# control_bat.net
KiCad netlist of a schematic drawn in EAGLE
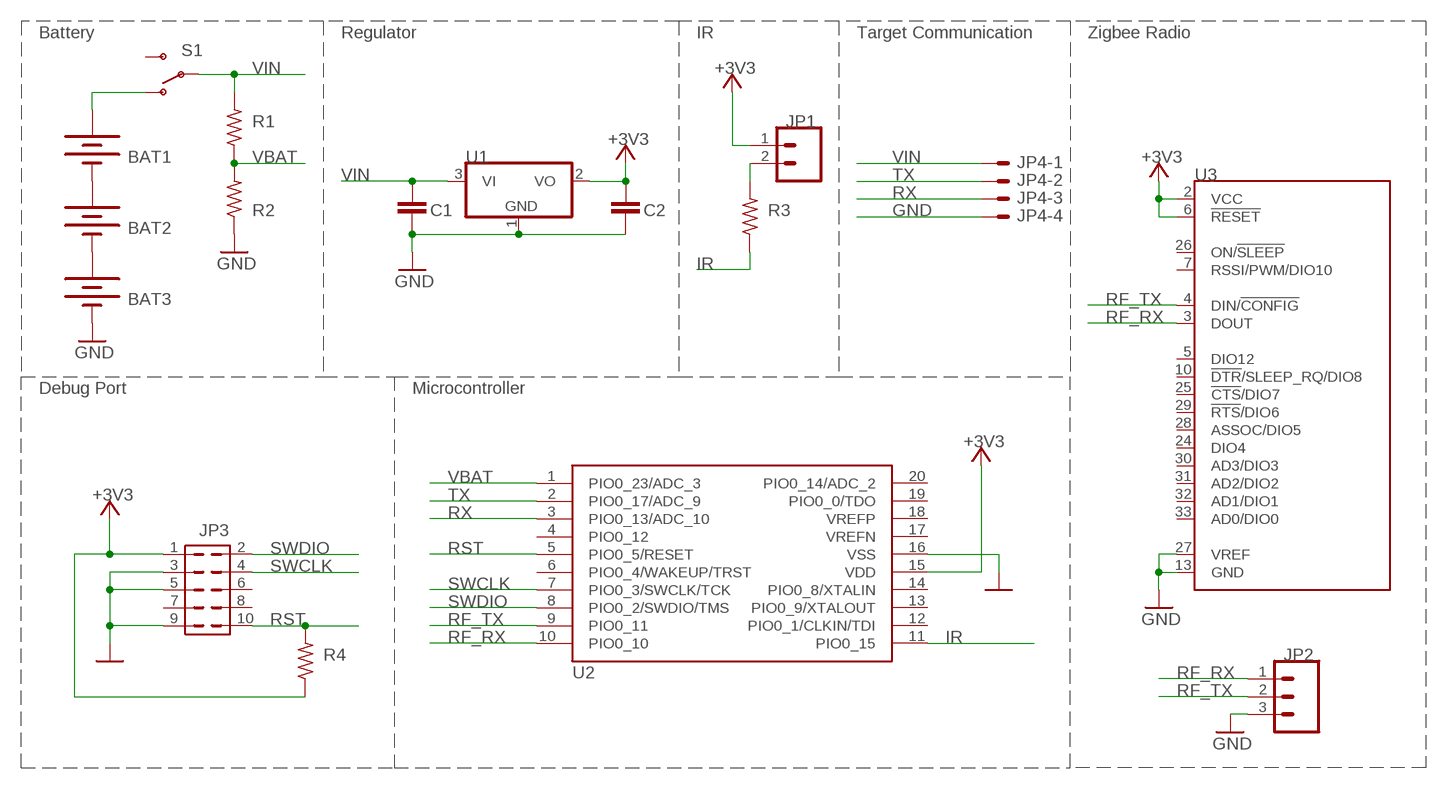
[diagram p0: schematic, sheet 1]

(export (version "E")
  (design (tool "Eeschema 10.0.6"))
  (components
    (comp (ref "BAT1")
      (value "BATTERYAAA-KIT")
      (footprint "eagle-import:BATTERY-AAA-KIT")
      (libsource (lib "eagle-import") (part "BATTERYAAA-KIT"))
    )
    (comp (ref "BAT2")
      (value "BATTERYAAA-KIT")
      (footprint "eagle-import:BATTERY-AAA-KIT")
      (libsource (lib "eagle-import") (part "BATTERYAAA-KIT"))
    )
    (comp (ref "BAT3")
      (value "BATTERYAAA-KIT")
      (footprint "eagle-import:BATTERY-AAA-KIT")
      (libsource (lib "eagle-import") (part "BATTERYAAA-KIT"))
    )
    (comp (ref "C1")
      (value "C1608X5R1C106M080AB")
      (footprint "eagle-import:0603-CAP")
      (libsource (lib "eagle-import") (part "CAP0603-CAP"))
    )
    (comp (ref "C2")
      (value "C1608X5R1C106M080AB")
      (footprint "eagle-import:0603-CAP")
      (libsource (lib "eagle-import") (part "CAP0603-CAP"))
    )
    (comp (ref "JP1")
      (value "M02PTH")
      (footprint "eagle-import:1X02")
      (libsource (lib "eagle-import") (part "M02PTH"))
    )
    (comp (ref "JP2")
      (value "M03PTH")
      (footprint "eagle-import:1X03")
      (libsource (lib "eagle-import") (part "M03PTH"))
    )
    (comp (ref "JP3")
      (value "FTSH-105-01-L")
      (footprint "eagle-import:FTSH-105-01-XXX-DV-K")
      (libsource (lib "eagle-import") (part "FTSH-105"))
    )
    (comp (ref "JP4")
      (value "798-DF134P125V20")
      (footprint "eagle-import:53398-04")
      (libsource (lib "eagle-import") (part "53?-04398"))
    )
    (comp (ref "R1")
      (value "71-CRCW0603-10K-E3")
      (footprint "eagle-import:R0603")
      (libsource (lib "eagle-import") (part "R-US_R0603"))
    )
    (comp (ref "R2")
      (value "71-CRCW0603-10K-E3")
      (footprint "eagle-import:R0603")
      (libsource (lib "eagle-import") (part "R-US_R0603"))
    )
    (comp (ref "R3")
      (value "71-CRCW0603220RFKEB")
      (footprint "eagle-import:R0603")
      (libsource (lib "eagle-import") (part "R-US_R0603"))
    )
    (comp (ref "R4")
      (value "71-CRCW0603-10K-E3")
      (footprint "eagle-import:R0603")
      (libsource (lib "eagle-import") (part "R-US_R0603"))
    )
    (comp (ref "S1")
      (value "612-EG1270")
      (footprint "eagle-import:EG1270")
      (libsource (lib "eagle-import") (part "SWITCH-SPST"))
    )
    (comp (ref "U1")
      (value "579-MCP1703T-3002ECB")
      (footprint "eagle-import:SOT23")
      (libsource (lib "eagle-import") (part "MCP1703CB"))
    )
    (comp (ref "U2")
      (value "771-LPC824M201JDH20J")
      (footprint "eagle-import:TSSOP20")
      (libsource (lib "eagle-import") (part "LPC824"))
    )
    (comp (ref "U3")
      (value "888-XB24CZ7PIS-004")
      (footprint "eagle-import:XBEE-SMT")
      (libsource (lib "eagle-import") (part "XBEE-SMT"))
    )
  )
  (nets
    (net (code "1") (name "+3V3") (class "Default")
      (node (ref "C2") (pin "1") (pinfunction "1_1") (pintype "passive"))
      (node (ref "JP1") (pin "1") (pinfunction "1_1") (pintype "passive"))
      (node (ref "JP3") (pin "1") (pinfunction "1_1") (pintype "passive"))
      (node (ref "R4") (pin "1") (pinfunction "1_1") (pintype "passive"))
      (node (ref "U1") (pin "2") (pinfunction "VO_2") (pintype "passive"))
      (node (ref "U2") (pin "15") (pinfunction "VDD_15") (pintype "bidirectional"))
      (node (ref "U3") (pin "2") (pinfunction "VCC_2") (pintype "power_in"))
      (node (ref "U3") (pin "6") (pinfunction "~{RESET}_6") (pintype "input"))
    )
    (net (code "2") (name "/IR") (class "Default")
      (node (ref "R3") (pin "1") (pinfunction "1_1") (pintype "passive"))
      (node (ref "U2") (pin "11") (pinfunction "PIO0_15_11") (pintype "bidirectional"))
    )
    (net (code "3") (name "/RF_RX") (class "Default")
      (node (ref "JP2") (pin "1") (pinfunction "1_1") (pintype "passive"))
      (node (ref "U2") (pin "10") (pinfunction "PIO0_10_10") (pintype "bidirectional"))
      (node (ref "U3") (pin "3") (pinfunction "DOUT_3") (pintype "output"))
    )
    (net (code "4") (name "/RF_TX") (class "Default")
      (node (ref "JP2") (pin "2") (pinfunction "2_2") (pintype "passive"))
      (node (ref "U2") (pin "9") (pinfunction "PIO0_11_9") (pintype "bidirectional"))
      (node (ref "U3") (pin "4") (pinfunction "DIN/~{CONFIG}_4") (pintype "input"))
    )
    (net (code "5") (name "/RST") (class "Default")
      (node (ref "JP3") (pin "10") (pinfunction "10_10") (pintype "passive"))
      (node (ref "R4") (pin "2") (pinfunction "2_2") (pintype "passive"))
      (node (ref "U2") (pin "5") (pinfunction "PIO0_5/RESET_5") (pintype "bidirectional"))
    )
    (net (code "6") (name "/RX") (class "Default")
      (node (ref "JP4") (pin "3") (pinfunction "S_3") (pintype "passive"))
      (node (ref "U2") (pin "3") (pinfunction "PIO0_13/ADC_10_3") (pintype "bidirectional"))
    )
    (net (code "7") (name "/SWCLK") (class "Default")
      (node (ref "JP3") (pin "4") (pinfunction "4_4") (pintype "passive"))
      (node (ref "U2") (pin "7") (pinfunction "PIO0_3/SWCLK/TCK_7") (pintype "bidirectional"))
    )
    (net (code "8") (name "/SWDIO") (class "Default")
      (node (ref "JP3") (pin "2") (pinfunction "2_2") (pintype "passive"))
      (node (ref "U2") (pin "8") (pinfunction "PIO0_2/SWDIO/TMS_8") (pintype "bidirectional"))
    )
    (net (code "9") (name "/TX") (class "Default")
      (node (ref "JP4") (pin "2") (pinfunction "S_2") (pintype "passive"))
      (node (ref "U2") (pin "2") (pinfunction "PIO0_17/ADC_9_2") (pintype "bidirectional"))
    )
    (net (code "10") (name "/VBAT") (class "Default")
      (node (ref "R1") (pin "1") (pinfunction "1_1") (pintype "passive"))
      (node (ref "R2") (pin "2") (pinfunction "2_2") (pintype "passive"))
      (node (ref "U2") (pin "1") (pinfunction "PIO0_23/ADC_3_1") (pintype "bidirectional"))
    )
    (net (code "11") (name "/VIN") (class "Default")
      (node (ref "C1") (pin "1") (pinfunction "1_1") (pintype "passive"))
      (node (ref "JP4") (pin "1") (pinfunction "S_1") (pintype "passive"))
      (node (ref "R1") (pin "2") (pinfunction "2_2") (pintype "passive"))
      (node (ref "S1") (pin "P$2") (pinfunction "P_P$2") (pintype "passive"))
      (node (ref "U1") (pin "3") (pinfunction "VI_3") (pintype "input"))
    )
    (net (code "12") (name "GND") (class "Default")
      (node (ref "BAT3") (pin "GND@1") (pinfunction "-_GND@1") (pintype "power_in"))
      (node (ref "C1") (pin "2") (pinfunction "2_2") (pintype "passive"))
      (node (ref "C2") (pin "2") (pinfunction "2_2") (pintype "passive"))
      (node (ref "JP2") (pin "3") (pinfunction "3_3") (pintype "passive"))
      (node (ref "JP3") (pin "3") (pinfunction "3_3") (pintype "passive"))
      (node (ref "JP3") (pin "5") (pinfunction "5_5") (pintype "passive"))
      (node (ref "JP3") (pin "9") (pinfunction "9_9") (pintype "passive"))
      (node (ref "JP4") (pin "4") (pinfunction "S_4") (pintype "passive"))
      (node (ref "R2") (pin "1") (pinfunction "1_1") (pintype "passive"))
      (node (ref "U1") (pin "1") (pinfunction "GND_1") (pintype "passive"))
      (node (ref "U2") (pin "16") (pinfunction "VSS_16") (pintype "bidirectional"))
      (node (ref "U3") (pin "13") (pinfunction "GND_13") (pintype "power_in"))
      (node (ref "U3") (pin "27") (pinfunction "VREF_27") (pintype "input"))
    )
    (net (code "13") (name "Net-(BAT1-+)") (class "Default")
      (node (ref "BAT1") (pin "PWR@1") (pinfunction "+_PWR@1") (pintype "power_in"))
      (node (ref "S1") (pin "P$1") (pinfunction "O_P$1") (pintype "passive"))
    )
    (net (code "14") (name "Net-(BAT1--)") (class "Default")
      (node (ref "BAT1") (pin "GND@1") (pinfunction "-_GND@1") (pintype "power_in"))
      (node (ref "BAT2") (pin "PWR@1") (pinfunction "+_PWR@1") (pintype "power_in"))
    )
    (net (code "15") (name "Net-(BAT2--)") (class "Default")
      (node (ref "BAT2") (pin "GND@1") (pinfunction "-_GND@1") (pintype "power_in"))
      (node (ref "BAT3") (pin "PWR@1") (pinfunction "+_PWR@1") (pintype "power_in"))
    )
    (net (code "16") (name "Net-(JP1-Pad2)") (class "Default")
      (node (ref "JP1") (pin "2") (pinfunction "2_2") (pintype "passive"))
      (node (ref "R3") (pin "2") (pinfunction "2_2") (pintype "passive"))
    )
    (net (code "17") (name "unconnected-(JP3-Pad6)") (class "Default")
      (node (ref "JP3") (pin "6") (pinfunction "6_6") (pintype "passive"))
    )
    (net (code "18") (name "unconnected-(JP3-Pad7)") (class "Default")
      (node (ref "JP3") (pin "7") (pinfunction "7_7") (pintype "passive"))
    )
    (net (code "19") (name "unconnected-(JP3-Pad8)") (class "Default")
      (node (ref "JP3") (pin "8") (pinfunction "8_8") (pintype "passive"))
    )
    (net (code "20") (name "unconnected-(S1-S-PadP$3)") (class "Default")
      (node (ref "S1") (pin "P$3") (pinfunction "S_P$3") (pintype "passive"))
    )
    (net (code "21") (name "unconnected-(U2-PIO0_0{slash}TDO-Pad19)") (class "Default")
      (node (ref "U2") (pin "19") (pinfunction "PIO0_0/TDO_19") (pintype "bidirectional"))
    )
    (net (code "22") (name "unconnected-(U2-PIO0_1{slash}CLKIN{slash}TDI-Pad12)") (class "Default")
      (node (ref "U2") (pin "12") (pinfunction "PIO0_1/CLKIN/TDI_12") (pintype "bidirectional"))
    )
    (net (code "23") (name "unconnected-(U2-PIO0_4{slash}WAKEUP{slash}TRST-Pad6)") (class "Default")
      (node (ref "U2") (pin "6") (pinfunction "PIO0_4/WAKEUP/TRST_6") (pintype "bidirectional"))
    )
    (net (code "24") (name "unconnected-(U2-PIO0_8{slash}XTALIN-Pad14)") (class "Default")
      (node (ref "U2") (pin "14") (pinfunction "PIO0_8/XTALIN_14") (pintype "bidirectional"))
    )
    (net (code "25") (name "unconnected-(U2-PIO0_9{slash}XTALOUT-Pad13)") (class "Default")
      (node (ref "U2") (pin "13") (pinfunction "PIO0_9/XTALOUT_13") (pintype "bidirectional"))
    )
    (net (code "26") (name "unconnected-(U2-PIO0_12-Pad4)") (class "Default")
      (node (ref "U2") (pin "4") (pinfunction "PIO0_12_4") (pintype "bidirectional"))
    )
    (net (code "27") (name "unconnected-(U2-PIO0_14{slash}ADC_2-Pad20)") (class "Default")
      (node (ref "U2") (pin "20") (pinfunction "PIO0_14/ADC_2_20") (pintype "bidirectional"))
    )
    (net (code "28") (name "unconnected-(U2-VREFN-Pad17)") (class "Default")
      (node (ref "U2") (pin "17") (pinfunction "VREFN_17") (pintype "bidirectional"))
    )
    (net (code "29") (name "unconnected-(U2-VREFP-Pad18)") (class "Default")
      (node (ref "U2") (pin "18") (pinfunction "VREFP_18") (pintype "bidirectional"))
    )
    (net (code "30") (name "unconnected-(U3-AD0{slash}DIO0-Pad33)") (class "Default")
      (node (ref "U3") (pin "33") (pinfunction "AD0/DIO0_33") (pintype "bidirectional"))
    )
    (net (code "31") (name "unconnected-(U3-AD1{slash}DIO1-Pad32)") (class "Default")
      (node (ref "U3") (pin "32") (pinfunction "AD1/DIO1_32") (pintype "bidirectional"))
    )
    (net (code "32") (name "unconnected-(U3-AD2{slash}DIO2-Pad31)") (class "Default")
      (node (ref "U3") (pin "31") (pinfunction "AD2/DIO2_31") (pintype "bidirectional"))
    )
    (net (code "33") (name "unconnected-(U3-AD3{slash}DIO3-Pad30)") (class "Default")
      (node (ref "U3") (pin "30") (pinfunction "AD3/DIO3_30") (pintype "bidirectional"))
    )
    (net (code "34") (name "unconnected-(U3-ASSOC{slash}DIO5-Pad28)") (class "Default")
      (node (ref "U3") (pin "28") (pinfunction "ASSOC/DIO5_28") (pintype "bidirectional"))
    )
    (net (code "35") (name "unconnected-(U3-DIO4-Pad24)") (class "Default")
      (node (ref "U3") (pin "24") (pinfunction "DIO4_24") (pintype "bidirectional"))
    )
    (net (code "36") (name "unconnected-(U3-DIO12-Pad5)") (class "Default")
      (node (ref "U3") (pin "5") (pinfunction "DIO12_5") (pintype "bidirectional"))
    )
    (net (code "37") (name "unconnected-(U3-ON{slash}~{SLEEP}-Pad26)") (class "Default")
      (node (ref "U3") (pin "26") (pinfunction "ON/~{SLEEP}_26") (pintype "output"))
    )
    (net (code "38") (name "unconnected-(U3-RSSI{slash}PWM{slash}DIO10-Pad7)") (class "Default")
      (node (ref "U3") (pin "7") (pinfunction "RSSI/PWM/DIO10_7") (pintype "output"))
    )
    (net (code "39") (name "unconnected-(U3-~{CTS}{slash}DIO7-Pad25)") (class "Default")
      (node (ref "U3") (pin "25") (pinfunction "~{CTS}/DIO7_25") (pintype "bidirectional"))
    )
    (net (code "40") (name "unconnected-(U3-~{DTR}{slash}SLEEP_RQ{slash}DIO8-Pad10)") (class "Default")
      (node (ref "U3") (pin "10") (pinfunction "~{DTR}/SLEEP_RQ/DIO8_10") (pintype "bidirectional"))
    )
    (net (code "41") (name "unconnected-(U3-~{RTS}{slash}DIO6-Pad29)") (class "Default")
      (node (ref "U3") (pin "29") (pinfunction "~{RTS}/DIO6_29") (pintype "bidirectional"))
    )
  )
)
